# Comparator.net
KiCad netlist of a schematic drawn in Altium Designer
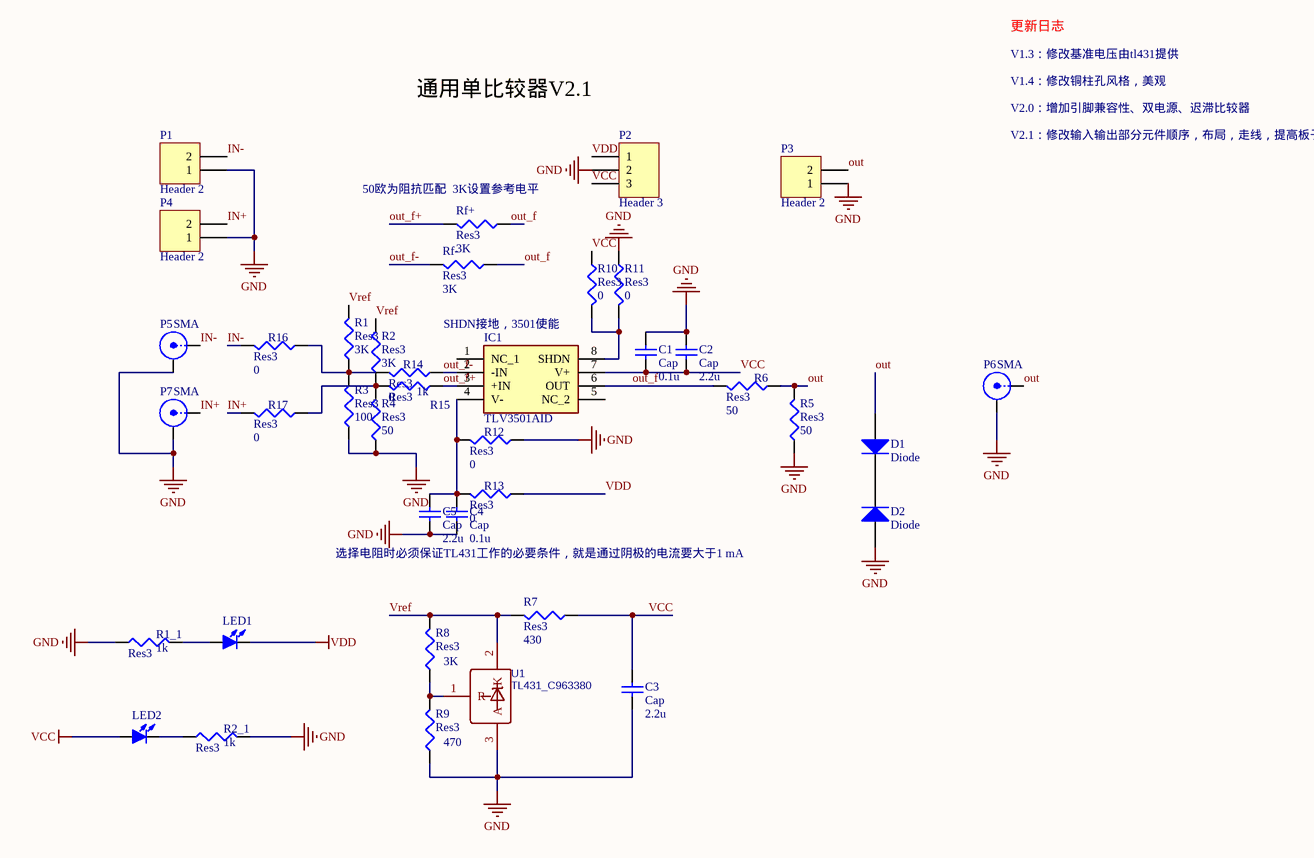
[diagram p0: Comparator.SchDoc]

(export (version "E")
  (design (tool "Eeschema 10.0.6"))
  (components
    (comp (ref "C1")
      (value "Cap")
      (footprint "0805D")
      (description "Capacitor")
      (fields (field (name "ALTIUM_VALUE") "0.1u") (field (name "PUBLISHER") "Altium Limited"))
      (libsource (lib "Miscellaneous Devices") (part "Cap"))
    )
    (comp (ref "C2")
      (value "Cap")
      (footprint "0805D")
      (description "Capacitor")
      (fields (field (name "ALTIUM_VALUE") "2.2u") (field (name "PUBLISHER") "Altium Limited"))
      (libsource (lib "Miscellaneous Devices") (part "Cap"))
    )
    (comp (ref "C3")
      (value "Cap")
      (footprint "0805D")
      (description "Capacitor")
      (fields (field (name "ALTIUM_VALUE") "2.2u") (field (name "PUBLISHER") "Altium Limited"))
      (libsource (lib "Miscellaneous Devices") (part "Cap"))
    )
    (comp (ref "C4")
      (value "Cap")
      (footprint "0805D")
      (description "Capacitor")
      (fields (field (name "ALTIUM_VALUE") "0.1u") (field (name "PUBLISHER") "Altium Limited"))
      (libsource (lib "Miscellaneous Devices") (part "Cap"))
    )
    (comp (ref "C5")
      (value "Cap")
      (footprint "0805D")
      (description "Capacitor")
      (fields (field (name "ALTIUM_VALUE") "2.2u") (field (name "PUBLISHER") "Altium Limited"))
      (libsource (lib "Miscellaneous Devices") (part "Cap"))
    )
    (comp (ref "D1")
      (value "Diode")
      (footprint "1206A")
      (description "Default Diode")
      (fields (field (name "PUBLISHER") "Altium Limited"))
      (libsource (lib "Miscellaneous Devices") (part "Diode"))
    )
    (comp (ref "D2")
      (value "Diode")
      (footprint "1206A")
      (description "Default Diode")
      (fields (field (name "PUBLISHER") "Altium Limited"))
      (libsource (lib "Miscellaneous Devices") (part "Diode"))
    )
    (comp (ref "IC1")
      (value "TLV3501AID")
      (footprint "SamacSys:SOIC127P600X175-8N")
      (description "Integrated Circuit")
      (fields (field (name "MOUSER PART NUMBER") "595-TLV3501AID"))
      (libsource (lib "SamacSys") (part "TLV3501AID"))
    )
    (comp (ref "LED1")
      (value "~")
      (footprint "0805D")
      (description "贴片LED")
      (fields (field (name "版权归属") "源创客"))
      (libsource (lib "LED") (part "LED-SMD"))
    )
    (comp (ref "LED2")
      (value "~")
      (footprint "0805D")
      (description "贴片LED")
      (fields (field (name "版权归属") "源创客"))
      (libsource (lib "LED") (part "LED-SMD"))
    )
    (comp (ref "P1")
      (value "Header 2")
      (footprint "HDR1X2")
      (description "Header, 2-Pin")
      (fields (field (name "PUBLISHER") "Altium Limited"))
      (libsource (lib "Miscellaneous Connectors") (part "Header 2"))
    )
    (comp (ref "P2")
      (value "Header 3")
      (footprint "HDR1X3")
      (description "Header, 3-Pin")
      (fields (field (name "PUBLISHER") "Altium Limited"))
      (libsource (lib "Miscellaneous Connectors") (part "Header 3"))
    )
    (comp (ref "P3")
      (value "Header 2")
      (footprint "HDR1X2")
      (description "Header, 2-Pin")
      (fields (field (name "PUBLISHER") "Altium Limited"))
      (libsource (lib "Miscellaneous Connectors") (part "Header 2"))
    )
    (comp (ref "P4")
      (value "Header 2")
      (footprint "HDR1X2")
      (description "Header, 2-Pin")
      (fields (field (name "PUBLISHER") "Altium Limited"))
      (libsource (lib "Miscellaneous Connectors") (part "Header 2"))
    )
    (comp (ref "P5")
      (value "SMA")
      (footprint "SMA1")
      (description "BNC Elbow Connector")
      (fields (field (name "PUBLISHER") "Altium Limited"))
      (libsource (lib "Miscellaneous Connectors") (part "BNC"))
    )
    (comp (ref "P6")
      (value "SMA")
      (footprint "SMA1")
      (description "BNC Elbow Connector")
      (fields (field (name "PUBLISHER") "Altium Limited"))
      (libsource (lib "Miscellaneous Connectors") (part "BNC"))
    )
    (comp (ref "P7")
      (value "SMA")
      (footprint "SMA1")
      (description "BNC Elbow Connector")
      (fields (field (name "PUBLISHER") "Altium Limited"))
      (libsource (lib "Miscellaneous Connectors") (part "BNC"))
    )
    (comp (ref "R1")
      (value "Res3")
      (footprint "0805D")
      (description "Resistor")
      (fields (field (name "ALTIUM_VALUE") "3K") (field (name "PUBLISHER") "Altium Limited"))
      (libsource (lib "Miscellaneous Devices") (part "Res3"))
    )
    (comp (ref "R1_1")
      (value "Res3")
      (footprint "0805D")
      (description "Resistor")
      (fields (field (name "ALTIUM_VALUE") "1k") (field (name "PUBLISHER") "Altium Limited"))
      (libsource (lib "Miscellaneous Devices") (part "Res3"))
    )
    (comp (ref "R2")
      (value "Res3")
      (footprint "0805D")
      (description "Resistor")
      (fields (field (name "ALTIUM_VALUE") "3K") (field (name "PUBLISHER") "Altium Limited"))
      (libsource (lib "Miscellaneous Devices") (part "Res3"))
    )
    (comp (ref "R2_1")
      (value "Res3")
      (footprint "0805D")
      (description "Resistor")
      (fields (field (name "ALTIUM_VALUE") "1k") (field (name "PUBLISHER") "Altium Limited"))
      (libsource (lib "Miscellaneous Devices") (part "Res3"))
    )
    (comp (ref "R3")
      (value "Res3")
      (footprint "0805D")
      (description "Resistor")
      (fields (field (name "ALTIUM_VALUE") "100") (field (name "PUBLISHER") "Altium Limited"))
      (libsource (lib "Miscellaneous Devices") (part "Res3"))
    )
    (comp (ref "R4")
      (value "Res3")
      (footprint "0805D")
      (description "Resistor")
      (fields (field (name "ALTIUM_VALUE") "50") (field (name "PUBLISHER") "Altium Limited"))
      (libsource (lib "Miscellaneous Devices") (part "Res3"))
    )
    (comp (ref "R5")
      (value "Res3")
      (footprint "0805D")
      (description "Resistor")
      (fields (field (name "ALTIUM_VALUE") "50") (field (name "PUBLISHER") "Altium Limited"))
      (libsource (lib "Miscellaneous Devices") (part "Res3"))
    )
    (comp (ref "R6")
      (value "Res3")
      (footprint "0805D")
      (description "Resistor")
      (fields (field (name "ALTIUM_VALUE") "50") (field (name "PUBLISHER") "Altium Limited"))
      (libsource (lib "Miscellaneous Devices") (part "Res3"))
    )
    (comp (ref "R7")
      (value "Res3")
      (footprint "0805D")
      (description "Resistor")
      (fields (field (name "ALTIUM_VALUE") "430") (field (name "PUBLISHER") "Altium Limited"))
      (libsource (lib "Miscellaneous Devices") (part "Res3"))
    )
    (comp (ref "R8")
      (value "Res3")
      (footprint "0805D")
      (description "Resistor")
      (fields (field (name "ALTIUM_VALUE") "3K") (field (name "PUBLISHER") "Altium Limited"))
      (libsource (lib "Miscellaneous Devices") (part "Res3"))
    )
    (comp (ref "R9")
      (value "Res3")
      (footprint "0805D")
      (description "Resistor")
      (fields (field (name "ALTIUM_VALUE") "470") (field (name "PUBLISHER") "Altium Limited"))
      (libsource (lib "Miscellaneous Devices") (part "Res3"))
    )
    (comp (ref "R10")
      (value "Res3")
      (footprint "0805D")
      (description "Resistor")
      (fields (field (name "ALTIUM_VALUE") "0") (field (name "PUBLISHER") "Altium Limited"))
      (libsource (lib "Miscellaneous Devices") (part "Res3"))
    )
    (comp (ref "R11")
      (value "Res3")
      (footprint "0805D")
      (description "Resistor")
      (fields (field (name "ALTIUM_VALUE") "0") (field (name "PUBLISHER") "Altium Limited"))
      (libsource (lib "Miscellaneous Devices") (part "Res3"))
    )
    (comp (ref "R12")
      (value "Res3")
      (footprint "0805D")
      (description "Resistor")
      (fields (field (name "ALTIUM_VALUE") "0") (field (name "PUBLISHER") "Altium Limited"))
      (libsource (lib "Miscellaneous Devices") (part "Res3"))
    )
    (comp (ref "R13")
      (value "Res3")
      (footprint "0805D")
      (description "Resistor")
      (fields (field (name "ALTIUM_VALUE") "0") (field (name "PUBLISHER") "Altium Limited"))
      (libsource (lib "Miscellaneous Devices") (part "Res3"))
    )
    (comp (ref "R14")
      (value "Res3")
      (footprint "0805D")
      (description "Resistor")
      (fields (field (name "ALTIUM_VALUE") "0") (field (name "PUBLISHER") "Altium Limited"))
      (libsource (lib "Miscellaneous Devices") (part "Res3"))
    )
    (comp (ref "R15")
      (value "Res3")
      (footprint "0805D")
      (description "Resistor")
      (fields (field (name "ALTIUM_VALUE") "1k") (field (name "PUBLISHER") "Altium Limited"))
      (libsource (lib "Miscellaneous Devices") (part "Res3"))
    )
    (comp (ref "R16")
      (value "Res3")
      (footprint "0805D")
      (description "Resistor")
      (fields (field (name "ALTIUM_VALUE") "0") (field (name "PUBLISHER") "Altium Limited"))
      (libsource (lib "Miscellaneous Devices") (part "Res3"))
    )
    (comp (ref "R17")
      (value "Res3")
      (footprint "0805D")
      (description "Resistor")
      (fields (field (name "ALTIUM_VALUE") "0") (field (name "PUBLISHER") "Altium Limited"))
      (libsource (lib "Miscellaneous Devices") (part "Res3"))
    )
    (comp (ref "Rf+")
      (value "Res3")
      (footprint "0805D")
      (description "Resistor")
      (fields (field (name "ALTIUM_VALUE") "3K") (field (name "PUBLISHER") "Altium Limited"))
      (libsource (lib "Miscellaneous Devices") (part "Res3"))
    )
    (comp (ref "Rf-")
      (value "Res3")
      (footprint "0805D")
      (description "Resistor")
      (fields (field (name "ALTIUM_VALUE") "3K") (field (name "PUBLISHER") "Altium Limited"))
      (libsource (lib "Miscellaneous Devices") (part "Res3"))
    )
    (comp (ref "U1")
      (value "TL431_C963380")
      (footprint "SOT-23")
      (fields
        (field (name "BOM_SUPPLIER PART") "C963380")
        (field (name "BOM_MANUFACTURER PART") "TL431")
        (field (name "CONTRIBUTOR") "LCSC")
      )
      (libsource (lib "TL431") (part "TL431"))
    )
  )
  (nets
    (net (code "1") (name "/IN+") (class "Default")
      (node (ref "P4") (pin "2") (pinfunction "2_2") (pintype "passive"))
      (node (ref "P7") (pin "1") (pinfunction "X_1") (pintype "passive"))
      (node (ref "R17") (pin "2") (pinfunction "2_2") (pintype "passive"))
    )
    (net (code "2") (name "/IN-") (class "Default")
      (node (ref "P1") (pin "2") (pinfunction "2_2") (pintype "passive"))
      (node (ref "P5") (pin "1") (pinfunction "X_1") (pintype "passive"))
      (node (ref "R16") (pin "2") (pinfunction "2_2") (pintype "passive"))
    )
    (net (code "3") (name "/Vref") (class "Default")
      (node (ref "R1") (pin "2") (pinfunction "2_2") (pintype "passive"))
      (node (ref "R2") (pin "2") (pinfunction "2_2") (pintype "passive"))
      (node (ref "R7") (pin "2") (pinfunction "2_2") (pintype "passive"))
      (node (ref "R8") (pin "2") (pinfunction "2_2") (pintype "passive"))
      (node (ref "U1") (pin "2") (pinfunction "K_2") (pintype "passive"))
    )
    (net (code "4") (name "/out") (class "Default")
      (node (ref "D1") (pin "1") (pinfunction "A_1") (pintype "passive"))
      (node (ref "P3") (pin "2") (pinfunction "2_2") (pintype "passive"))
      (node (ref "P6") (pin "1") (pinfunction "X_1") (pintype "passive"))
      (node (ref "R5") (pin "2") (pinfunction "2_2") (pintype "passive"))
      (node (ref "R6") (pin "1") (pinfunction "1_1") (pintype "passive"))
    )
    (net (code "5") (name "/out_f") (class "Default")
      (node (ref "IC1") (pin "6") (pinfunction "OUT_6") (pintype "passive"))
      (node (ref "R6") (pin "2") (pinfunction "2_2") (pintype "passive"))
      (node (ref "Rf+") (pin "1") (pinfunction "1_1") (pintype "passive"))
      (node (ref "Rf-") (pin "1") (pinfunction "1_1") (pintype "passive"))
    )
    (net (code "6") (name "/out_f+") (class "Default")
      (node (ref "IC1") (pin "3") (pinfunction "+IN_3") (pintype "passive"))
      (node (ref "R15") (pin "1") (pinfunction "1_1") (pintype "passive"))
      (node (ref "Rf+") (pin "2") (pinfunction "2_2") (pintype "passive"))
    )
    (net (code "7") (name "/out_f-") (class "Default")
      (node (ref "IC1") (pin "2") (pinfunction "-IN_2") (pintype "passive"))
      (node (ref "R14") (pin "1") (pinfunction "1_1") (pintype "passive"))
      (node (ref "Rf-") (pin "2") (pinfunction "2_2") (pintype "passive"))
    )
    (net (code "8") (name "GND") (class "Default")
      (node (ref "C1") (pin "2") (pinfunction "2_2") (pintype "passive"))
      (node (ref "C2") (pin "2") (pinfunction "2_2") (pintype "passive"))
      (node (ref "C3") (pin "1") (pinfunction "1_1") (pintype "passive"))
      (node (ref "C4") (pin "2") (pinfunction "2_2") (pintype "passive"))
      (node (ref "C5") (pin "1") (pinfunction "1_1") (pintype "passive"))
      (node (ref "D2") (pin "1") (pinfunction "A_1") (pintype "passive"))
      (node (ref "P1") (pin "1") (pinfunction "1_1") (pintype "passive"))
      (node (ref "P2") (pin "2") (pinfunction "2_2") (pintype "passive"))
      (node (ref "P3") (pin "1") (pinfunction "1_1") (pintype "passive"))
      (node (ref "P4") (pin "1") (pinfunction "1_1") (pintype "passive"))
      (node (ref "P5") (pin "2") (pinfunction "Y_2") (pintype "passive"))
      (node (ref "P6") (pin "2") (pinfunction "Y_2") (pintype "passive"))
      (node (ref "P7") (pin "2") (pinfunction "Y_2") (pintype "passive"))
      (node (ref "R11") (pin "1") (pinfunction "1_1") (pintype "passive"))
      (node (ref "R12") (pin "1") (pinfunction "1_1") (pintype "passive"))
      (node (ref "R1_1") (pin "1") (pinfunction "1_1") (pintype "passive"))
      (node (ref "R2_1") (pin "2") (pinfunction "2_2") (pintype "passive"))
      (node (ref "R3") (pin "1") (pinfunction "1_1") (pintype "passive"))
      (node (ref "R4") (pin "1") (pinfunction "1_1") (pintype "passive"))
      (node (ref "R5") (pin "1") (pinfunction "1_1") (pintype "passive"))
      (node (ref "R9") (pin "1") (pinfunction "1_1") (pintype "passive"))
      (node (ref "U1") (pin "3") (pinfunction "A_3") (pintype "passive"))
    )
    (net (code "9") (name "Net-(D1-K)") (class "Default")
      (node (ref "D1") (pin "2") (pinfunction "K_2") (pintype "passive"))
      (node (ref "D2") (pin "2") (pinfunction "K_2") (pintype "passive"))
    )
    (net (code "10") (name "Net-(IC1-SHDN)") (class "Default")
      (node (ref "IC1") (pin "8") (pinfunction "SHDN_8") (pintype "passive"))
      (node (ref "R10") (pin "2") (pinfunction "2_2") (pintype "passive"))
      (node (ref "R11") (pin "2") (pinfunction "2_2") (pintype "passive"))
    )
    (net (code "11") (name "Net-(IC1-V-)") (class "Default")
      (node (ref "C4") (pin "1") (pinfunction "1_1") (pintype "passive"))
      (node (ref "C5") (pin "2") (pinfunction "2_2") (pintype "passive"))
      (node (ref "IC1") (pin "4") (pinfunction "V-_4") (pintype "passive"))
      (node (ref "R12") (pin "2") (pinfunction "2_2") (pintype "passive"))
      (node (ref "R13") (pin "2") (pinfunction "2_2") (pintype "passive"))
    )
    (net (code "12") (name "Net-(LED1-A)") (class "Default")
      (node (ref "LED1") (pin "1") (pinfunction "A_1") (pintype "passive"))
      (node (ref "R1_1") (pin "2") (pinfunction "2_2") (pintype "passive"))
    )
    (net (code "13") (name "Net-(LED2-K)") (class "Default")
      (node (ref "LED2") (pin "2") (pinfunction "K_2") (pintype "passive"))
      (node (ref "R2_1") (pin "1") (pinfunction "1_1") (pintype "passive"))
    )
    (net (code "14") (name "Net-(R1-Pad1)") (class "Default")
      (node (ref "R1") (pin "1") (pinfunction "1_1") (pintype "passive"))
      (node (ref "R14") (pin "2") (pinfunction "2_2") (pintype "passive"))
      (node (ref "R16") (pin "1") (pinfunction "1_1") (pintype "passive"))
      (node (ref "R3") (pin "2") (pinfunction "2_2") (pintype "passive"))
    )
    (net (code "15") (name "Net-(R15-Pad2)") (class "Default")
      (node (ref "R15") (pin "2") (pinfunction "2_2") (pintype "passive"))
      (node (ref "R17") (pin "1") (pinfunction "1_1") (pintype "passive"))
      (node (ref "R2") (pin "1") (pinfunction "1_1") (pintype "passive"))
      (node (ref "R4") (pin "2") (pinfunction "2_2") (pintype "passive"))
    )
    (net (code "16") (name "Net-(U1-R)") (class "Default")
      (node (ref "R8") (pin "1") (pinfunction "1_1") (pintype "passive"))
      (node (ref "R9") (pin "2") (pinfunction "2_2") (pintype "passive"))
      (node (ref "U1") (pin "1") (pinfunction "R_1") (pintype "passive"))
    )
    (net (code "17") (name "VCC") (class "Default")
      (node (ref "C1") (pin "1") (pinfunction "1_1") (pintype "passive"))
      (node (ref "C2") (pin "1") (pinfunction "1_1") (pintype "passive"))
      (node (ref "C3") (pin "2") (pinfunction "2_2") (pintype "passive"))
      (node (ref "IC1") (pin "7") (pinfunction "V+_7") (pintype "passive"))
      (node (ref "LED2") (pin "1") (pinfunction "A_1") (pintype "passive"))
      (node (ref "P2") (pin "3") (pinfunction "3_3") (pintype "passive"))
      (node (ref "R10") (pin "1") (pinfunction "1_1") (pintype "passive"))
      (node (ref "R7") (pin "1") (pinfunction "1_1") (pintype "passive"))
    )
    (net (code "18") (name "VDD") (class "Default")
      (node (ref "LED1") (pin "2") (pinfunction "K_2") (pintype "passive"))
      (node (ref "P2") (pin "1") (pinfunction "1_1") (pintype "passive"))
      (node (ref "R13") (pin "1") (pinfunction "1_1") (pintype "passive"))
    )
    (net (code "19") (name "unconnected-(IC1-NC_1-Pad1)") (class "Default")
      (node (ref "IC1") (pin "1") (pinfunction "NC_1_1") (pintype "passive"))
    )
    (net (code "20") (name "unconnected-(IC1-NC_2-Pad5)") (class "Default")
      (node (ref "IC1") (pin "5") (pinfunction "NC_2_5") (pintype "passive"))
    )
  )
)
